# ICM-20948.net
KiCad netlist of a schematic drawn in Altium Designer
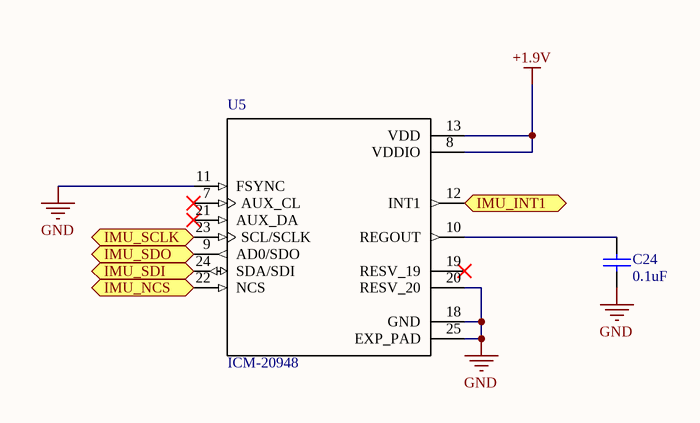
[diagram p0: ICM-20948.SchDoc]

(export (version "E")
  (design (tool "Eeschema 10.0.6"))
  (components
    (comp (ref "C24")
      (value "0.1uF")
      (footprint "0201_Custom")
      (description "Capacitor (Semiconductor SIM Model)")
      (fields (field (name "PUBLISHER") "Altium Limited"))
      (libsource (lib "Miscellaneous Devices") (part "Cap Semi"))
    )
    (comp (ref "U5")
      (value "ICM-20948")
      (footprint "ICM-20948")
      (description "9 Axis=3 Axis Gyro+3 Axis Accel+Compass. Pin For Pin With m")
      (fields (field (name "DIGI-KEY_PART_NUMBER") "1428-1123-1-ND") (field (name "MF") "TDK InvenSense"))
      (libsource (lib "ICM-20948") (part "ICM-20948"))
    )
  )
  (nets
    (net (code "1") (name "+1.9V") (class "Default")
      (node (ref "U5") (pin "13") (pinfunction "VDD_13") (pintype "power_in"))
      (node (ref "U5") (pin "8") (pinfunction "VDDIO_8") (pintype "power_in"))
    )
    (net (code "2") (name "/IMU_INT1") (class "Default")
      (node (ref "U5") (pin "12") (pinfunction "INT1_12") (pintype "output"))
    )
    (net (code "3") (name "/IMU_NCS") (class "Default")
      (node (ref "U5") (pin "22") (pinfunction "NCS_22") (pintype "input"))
    )
    (net (code "4") (name "/IMU_SCLK") (class "Default")
      (node (ref "U5") (pin "23") (pinfunction "SCL/SCLK_23") (pintype "input"))
    )
    (net (code "5") (name "/IMU_SDI") (class "Default")
      (node (ref "U5") (pin "24") (pinfunction "SDA/SDI_24") (pintype "bidirectional"))
    )
    (net (code "6") (name "/IMU_SDO") (class "Default")
      (node (ref "U5") (pin "9") (pinfunction "AD0/SDO_9") (pintype "output"))
    )
    (net (code "7") (name "GND") (class "Default")
      (node (ref "C24") (pin "2") (pinfunction "2_2") (pintype "passive"))
      (node (ref "U5") (pin "11") (pinfunction "FSYNC_11") (pintype "input"))
      (node (ref "U5") (pin "18") (pinfunction "GND_18") (pintype "power_in"))
      (node (ref "U5") (pin "20") (pinfunction "RESV_20_20") (pintype "passive"))
      (node (ref "U5") (pin "25") (pinfunction "EXP_PAD_25") (pintype "power_in"))
    )
    (net (code "8") (name "Net-(U5-REGOUT)") (class "Default")
      (node (ref "C24") (pin "1") (pinfunction "1_1") (pintype "passive"))
      (node (ref "U5") (pin "10") (pinfunction "REGOUT_10") (pintype "output"))
    )
    (net (code "9") (name "unconnected-(U5-AUX_CL-Pad7)") (class "Default")
      (node (ref "U5") (pin "7") (pinfunction "AUX_CL_7") (pintype "input+no_connect"))
    )
    (net (code "10") (name "unconnected-(U5-AUX_DA-Pad21)") (class "Default")
      (node (ref "U5") (pin "21") (pinfunction "AUX_DA_21") (pintype "input+no_connect"))
    )
    (net (code "11") (name "unconnected-(U5-RESV_19-Pad19)") (class "Default")
      (node (ref "U5") (pin "19") (pinfunction "RESV_19_19") (pintype "passive+no_connect"))
    )
  )
)
